# cable-concentrator.net
KiCad netlist of a schematic drawn in EAGLE
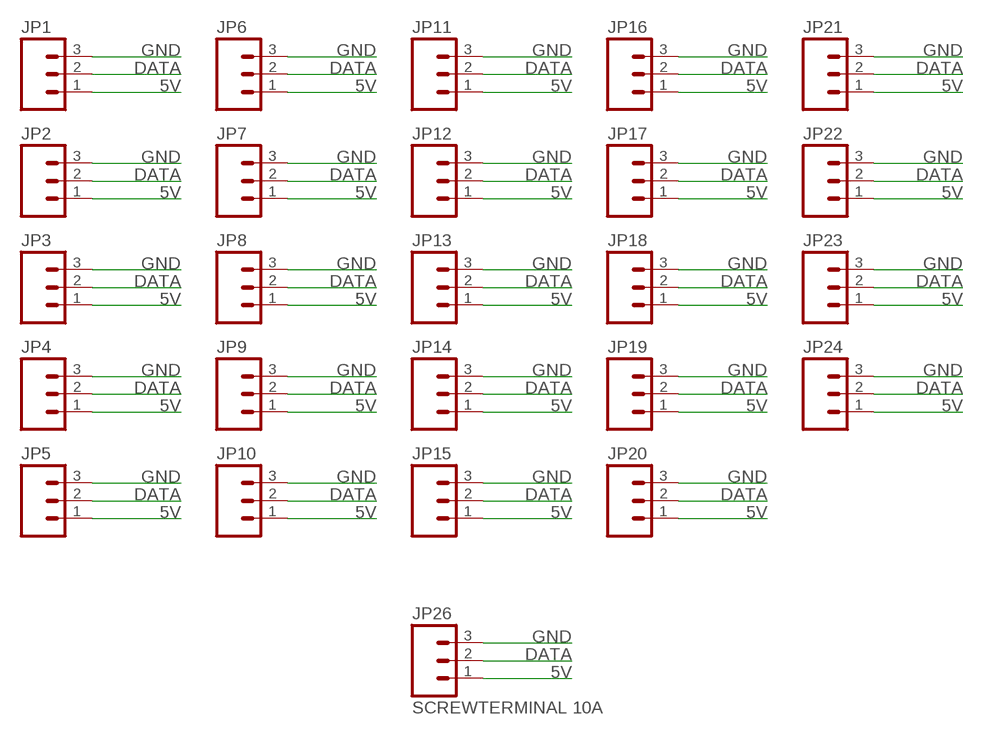
[diagram p0: schematic, sheet 1]

(export (version "E")
  (design (tool "Eeschema 10.0.6"))
  (components
    (comp (ref "JP1")
      (value "M03PTH")
      (footprint "eagle-import:1X03")
      (libsource (lib "eagle-import") (part "M03PTH"))
    )
    (comp (ref "JP2")
      (value "M03PTH")
      (footprint "eagle-import:1X03")
      (libsource (lib "eagle-import") (part "M03PTH"))
    )
    (comp (ref "JP3")
      (value "M03PTH")
      (footprint "eagle-import:1X03")
      (libsource (lib "eagle-import") (part "M03PTH"))
    )
    (comp (ref "JP4")
      (value "M03PTH")
      (footprint "eagle-import:1X03")
      (libsource (lib "eagle-import") (part "M03PTH"))
    )
    (comp (ref "JP5")
      (value "M03PTH")
      (footprint "eagle-import:1X03")
      (libsource (lib "eagle-import") (part "M03PTH"))
    )
    (comp (ref "JP6")
      (value "M03PTH")
      (footprint "eagle-import:1X03")
      (libsource (lib "eagle-import") (part "M03PTH"))
    )
    (comp (ref "JP7")
      (value "M03PTH")
      (footprint "eagle-import:1X03")
      (libsource (lib "eagle-import") (part "M03PTH"))
    )
    (comp (ref "JP8")
      (value "M03PTH")
      (footprint "eagle-import:1X03")
      (libsource (lib "eagle-import") (part "M03PTH"))
    )
    (comp (ref "JP9")
      (value "M03PTH")
      (footprint "eagle-import:1X03")
      (libsource (lib "eagle-import") (part "M03PTH"))
    )
    (comp (ref "JP10")
      (value "M03PTH")
      (footprint "eagle-import:1X03")
      (libsource (lib "eagle-import") (part "M03PTH"))
    )
    (comp (ref "JP11")
      (value "M03PTH")
      (footprint "eagle-import:1X03")
      (libsource (lib "eagle-import") (part "M03PTH"))
    )
    (comp (ref "JP12")
      (value "M03PTH")
      (footprint "eagle-import:1X03")
      (libsource (lib "eagle-import") (part "M03PTH"))
    )
    (comp (ref "JP13")
      (value "M03PTH")
      (footprint "eagle-import:1X03")
      (libsource (lib "eagle-import") (part "M03PTH"))
    )
    (comp (ref "JP14")
      (value "M03PTH")
      (footprint "eagle-import:1X03")
      (libsource (lib "eagle-import") (part "M03PTH"))
    )
    (comp (ref "JP15")
      (value "M03PTH")
      (footprint "eagle-import:1X03")
      (libsource (lib "eagle-import") (part "M03PTH"))
    )
    (comp (ref "JP16")
      (value "M03PTH")
      (footprint "eagle-import:1X03")
      (libsource (lib "eagle-import") (part "M03PTH"))
    )
    (comp (ref "JP17")
      (value "M03PTH")
      (footprint "eagle-import:1X03")
      (libsource (lib "eagle-import") (part "M03PTH"))
    )
    (comp (ref "JP18")
      (value "M03PTH")
      (footprint "eagle-import:1X03")
      (libsource (lib "eagle-import") (part "M03PTH"))
    )
    (comp (ref "JP19")
      (value "M03PTH")
      (footprint "eagle-import:1X03")
      (libsource (lib "eagle-import") (part "M03PTH"))
    )
    (comp (ref "JP20")
      (value "M03PTH")
      (footprint "eagle-import:1X03")
      (libsource (lib "eagle-import") (part "M03PTH"))
    )
    (comp (ref "JP21")
      (value "M03PTH")
      (footprint "eagle-import:1X03")
      (libsource (lib "eagle-import") (part "M03PTH"))
    )
    (comp (ref "JP22")
      (value "M03PTH")
      (footprint "eagle-import:1X03")
      (libsource (lib "eagle-import") (part "M03PTH"))
    )
    (comp (ref "JP23")
      (value "M03PTH")
      (footprint "eagle-import:1X03")
      (libsource (lib "eagle-import") (part "M03PTH"))
    )
    (comp (ref "JP24")
      (value "M03PTH")
      (footprint "eagle-import:1X03")
      (libsource (lib "eagle-import") (part "M03PTH"))
    )
    (comp (ref "JP26")
      (value "SCREWTERMINAL 10A")
      (footprint "eagle-import:SCREWTERMINAL-3.5MM-3")
      (libsource (lib "eagle-import") (part "M03SCREW"))
    )
  )
  (nets
    (net (code "1") (name "/5V") (class "Default")
      (node (ref "JP1") (pin "1") (pinfunction "1_1") (pintype "passive"))
      (node (ref "JP10") (pin "1") (pinfunction "1_1") (pintype "passive"))
      (node (ref "JP11") (pin "1") (pinfunction "1_1") (pintype "passive"))
      (node (ref "JP12") (pin "1") (pinfunction "1_1") (pintype "passive"))
      (node (ref "JP13") (pin "1") (pinfunction "1_1") (pintype "passive"))
      (node (ref "JP14") (pin "1") (pinfunction "1_1") (pintype "passive"))
      (node (ref "JP15") (pin "1") (pinfunction "1_1") (pintype "passive"))
      (node (ref "JP16") (pin "1") (pinfunction "1_1") (pintype "passive"))
      (node (ref "JP17") (pin "1") (pinfunction "1_1") (pintype "passive"))
      (node (ref "JP18") (pin "1") (pinfunction "1_1") (pintype "passive"))
      (node (ref "JP19") (pin "1") (pinfunction "1_1") (pintype "passive"))
      (node (ref "JP2") (pin "1") (pinfunction "1_1") (pintype "passive"))
      (node (ref "JP20") (pin "1") (pinfunction "1_1") (pintype "passive"))
      (node (ref "JP21") (pin "1") (pinfunction "1_1") (pintype "passive"))
      (node (ref "JP22") (pin "1") (pinfunction "1_1") (pintype "passive"))
      (node (ref "JP23") (pin "1") (pinfunction "1_1") (pintype "passive"))
      (node (ref "JP24") (pin "1") (pinfunction "1_1") (pintype "passive"))
      (node (ref "JP26") (pin "1") (pinfunction "1_1") (pintype "passive"))
      (node (ref "JP3") (pin "1") (pinfunction "1_1") (pintype "passive"))
      (node (ref "JP4") (pin "1") (pinfunction "1_1") (pintype "passive"))
      (node (ref "JP5") (pin "1") (pinfunction "1_1") (pintype "passive"))
      (node (ref "JP6") (pin "1") (pinfunction "1_1") (pintype "passive"))
      (node (ref "JP7") (pin "1") (pinfunction "1_1") (pintype "passive"))
      (node (ref "JP8") (pin "1") (pinfunction "1_1") (pintype "passive"))
      (node (ref "JP9") (pin "1") (pinfunction "1_1") (pintype "passive"))
    )
    (net (code "2") (name "/DATA") (class "Default")
      (node (ref "JP1") (pin "2") (pinfunction "2_2") (pintype "passive"))
      (node (ref "JP10") (pin "2") (pinfunction "2_2") (pintype "passive"))
      (node (ref "JP11") (pin "2") (pinfunction "2_2") (pintype "passive"))
      (node (ref "JP12") (pin "2") (pinfunction "2_2") (pintype "passive"))
      (node (ref "JP13") (pin "2") (pinfunction "2_2") (pintype "passive"))
      (node (ref "JP14") (pin "2") (pinfunction "2_2") (pintype "passive"))
      (node (ref "JP15") (pin "2") (pinfunction "2_2") (pintype "passive"))
      (node (ref "JP16") (pin "2") (pinfunction "2_2") (pintype "passive"))
      (node (ref "JP17") (pin "2") (pinfunction "2_2") (pintype "passive"))
      (node (ref "JP18") (pin "2") (pinfunction "2_2") (pintype "passive"))
      (node (ref "JP19") (pin "2") (pinfunction "2_2") (pintype "passive"))
      (node (ref "JP2") (pin "2") (pinfunction "2_2") (pintype "passive"))
      (node (ref "JP20") (pin "2") (pinfunction "2_2") (pintype "passive"))
      (node (ref "JP21") (pin "2") (pinfunction "2_2") (pintype "passive"))
      (node (ref "JP22") (pin "2") (pinfunction "2_2") (pintype "passive"))
      (node (ref "JP23") (pin "2") (pinfunction "2_2") (pintype "passive"))
      (node (ref "JP24") (pin "2") (pinfunction "2_2") (pintype "passive"))
      (node (ref "JP26") (pin "2") (pinfunction "2_2") (pintype "passive"))
      (node (ref "JP3") (pin "2") (pinfunction "2_2") (pintype "passive"))
      (node (ref "JP4") (pin "2") (pinfunction "2_2") (pintype "passive"))
      (node (ref "JP5") (pin "2") (pinfunction "2_2") (pintype "passive"))
      (node (ref "JP6") (pin "2") (pinfunction "2_2") (pintype "passive"))
      (node (ref "JP7") (pin "2") (pinfunction "2_2") (pintype "passive"))
      (node (ref "JP8") (pin "2") (pinfunction "2_2") (pintype "passive"))
      (node (ref "JP9") (pin "2") (pinfunction "2_2") (pintype "passive"))
    )
    (net (code "3") (name "/GND") (class "Default")
      (node (ref "JP1") (pin "3") (pinfunction "3_3") (pintype "passive"))
      (node (ref "JP10") (pin "3") (pinfunction "3_3") (pintype "passive"))
      (node (ref "JP11") (pin "3") (pinfunction "3_3") (pintype "passive"))
      (node (ref "JP12") (pin "3") (pinfunction "3_3") (pintype "passive"))
      (node (ref "JP13") (pin "3") (pinfunction "3_3") (pintype "passive"))
      (node (ref "JP14") (pin "3") (pinfunction "3_3") (pintype "passive"))
      (node (ref "JP15") (pin "3") (pinfunction "3_3") (pintype "passive"))
      (node (ref "JP16") (pin "3") (pinfunction "3_3") (pintype "passive"))
      (node (ref "JP17") (pin "3") (pinfunction "3_3") (pintype "passive"))
      (node (ref "JP18") (pin "3") (pinfunction "3_3") (pintype "passive"))
      (node (ref "JP19") (pin "3") (pinfunction "3_3") (pintype "passive"))
      (node (ref "JP2") (pin "3") (pinfunction "3_3") (pintype "passive"))
      (node (ref "JP20") (pin "3") (pinfunction "3_3") (pintype "passive"))
      (node (ref "JP21") (pin "3") (pinfunction "3_3") (pintype "passive"))
      (node (ref "JP22") (pin "3") (pinfunction "3_3") (pintype "passive"))
      (node (ref "JP23") (pin "3") (pinfunction "3_3") (pintype "passive"))
      (node (ref "JP24") (pin "3") (pinfunction "3_3") (pintype "passive"))
      (node (ref "JP26") (pin "3") (pinfunction "3_3") (pintype "passive"))
      (node (ref "JP3") (pin "3") (pinfunction "3_3") (pintype "passive"))
      (node (ref "JP4") (pin "3") (pinfunction "3_3") (pintype "passive"))
      (node (ref "JP5") (pin "3") (pinfunction "3_3") (pintype "passive"))
      (node (ref "JP6") (pin "3") (pinfunction "3_3") (pintype "passive"))
      (node (ref "JP7") (pin "3") (pinfunction "3_3") (pintype "passive"))
      (node (ref "JP8") (pin "3") (pinfunction "3_3") (pintype "passive"))
      (node (ref "JP9") (pin "3") (pinfunction "3_3") (pintype "passive"))
    )
  )
)
